# EnvironmentMonitorV6_0.net
KiCad netlist of a schematic drawn in EAGLE
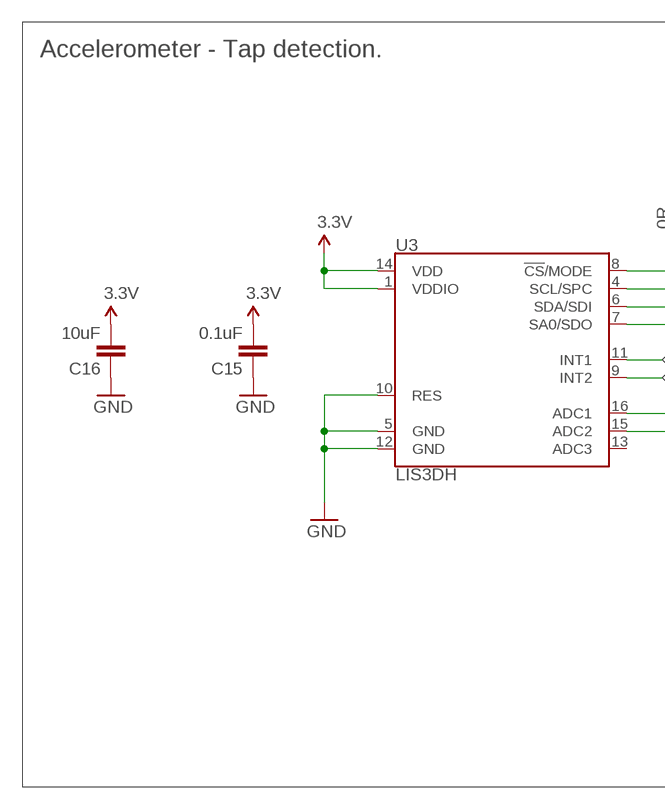
[diagram p0: schematic, sheet 1, part 1 of 2]
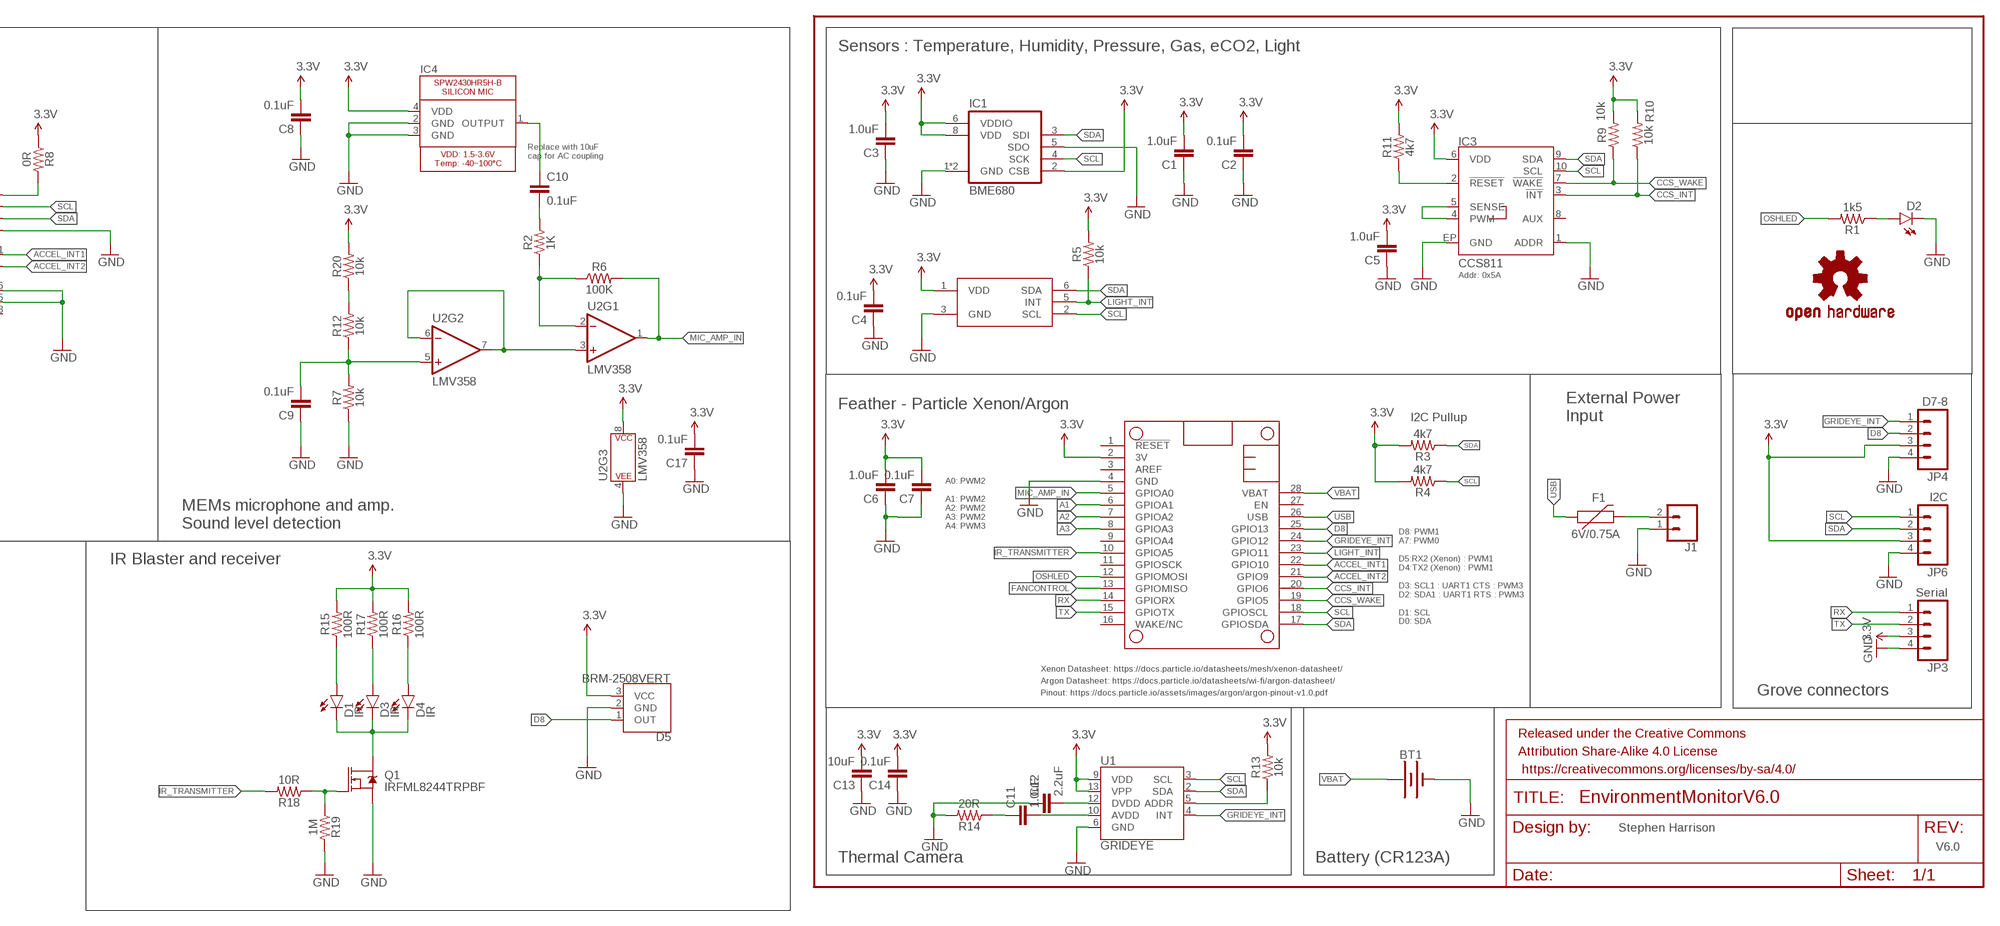
[diagram p1: schematic, sheet 1, part 2 of 2]

(export (version "E")
  (design (tool "Eeschema 10.0.6"))
  (components
    (comp (ref "BT1")
      (value "BATTERY-16340")
      (footprint "eagle-import:BATTERY_16340-HOLDER")
      (libsource (lib "eagle-import") (part "BATTERY-16340"))
    )
    (comp (ref "C1")
      (value "1.0uF")
      (footprint "eagle-import:0805-CAP")
      (libsource (lib "eagle-import") (part "1.0UF-25V-+80/-20(0805){dblquote}"))
    )
    (comp (ref "C2")
      (value "0.1uF")
      (footprint "eagle-import:0805-CAP")
      (libsource (lib "eagle-import") (part "1.0UF-25V-+80/-20(0805){dblquote}"))
    )
    (comp (ref "C3")
      (value "1.0uF")
      (footprint "eagle-import:0805-CAP")
      (libsource (lib "eagle-import") (part "1.0UF-25V-+80/-20(0805){dblquote}"))
    )
    (comp (ref "C4")
      (value "0.1uF")
      (footprint "eagle-import:0805-CAP")
      (libsource (lib "eagle-import") (part "1.0UF-25V-+80/-20(0805){dblquote}"))
    )
    (comp (ref "C5")
      (value "1.0uF")
      (footprint "eagle-import:0805-CAP")
      (libsource (lib "eagle-import") (part "1.0UF-25V-+80/-20(0805){dblquote}"))
    )
    (comp (ref "C6")
      (value "1.0uF")
      (footprint "eagle-import:0805-CAP")
      (libsource (lib "eagle-import") (part "1.0UF-25V-+80/-20(0805){dblquote}"))
    )
    (comp (ref "C7")
      (value "0.1uF")
      (footprint "eagle-import:0805-CAP")
      (libsource (lib "eagle-import") (part "1.0UF-25V-+80/-20(0805){dblquote}"))
    )
    (comp (ref "C8")
      (value "0.1uF")
      (footprint "eagle-import:0805-CAP")
      (libsource (lib "eagle-import") (part "1.0UF-25V-+80/-20(0805){dblquote}"))
    )
    (comp (ref "C9")
      (value "0.1uF")
      (footprint "eagle-import:0805-CAP")
      (libsource (lib "eagle-import") (part "1.0UF-25V-+80/-20(0805){dblquote}"))
    )
    (comp (ref "C10")
      (value "0.1uF")
      (footprint "eagle-import:0805-CAP")
      (libsource (lib "eagle-import") (part "1.0UF-25V-+80/-20(0805){dblquote}"))
    )
    (comp (ref "C11")
      (value "1.0uF")
      (footprint "eagle-import:0805-CAP")
      (libsource (lib "eagle-import") (part "1.0UF-25V-+80/-20(0805){dblquote}"))
    )
    (comp (ref "C12")
      (value "2.2uF")
      (footprint "eagle-import:0805-CAP")
      (libsource (lib "eagle-import") (part "1.0UF-25V-+80/-20(0805){dblquote}"))
    )
    (comp (ref "C13")
      (value "10uF")
      (footprint "eagle-import:0805-CAP")
      (libsource (lib "eagle-import") (part "1.0UF-25V-+80/-20(0805){dblquote}"))
    )
    (comp (ref "C14")
      (value "0.1uF")
      (footprint "eagle-import:0805-CAP")
      (libsource (lib "eagle-import") (part "1.0UF-25V-+80/-20(0805){dblquote}"))
    )
    (comp (ref "C15")
      (value "0.1uF")
      (footprint "eagle-import:0805-CAP")
      (libsource (lib "eagle-import") (part "1.0UF-25V-+80/-20(0805){dblquote}"))
    )
    (comp (ref "C16")
      (value "10uF")
      (footprint "eagle-import:0805-CAP")
      (libsource (lib "eagle-import") (part "1.0UF-25V-+80/-20(0805){dblquote}"))
    )
    (comp (ref "C17")
      (value "0.1uF")
      (footprint "eagle-import:0805-CAP")
      (libsource (lib "eagle-import") (part "1.0UF-25V-+80/-20(0805){dblquote}"))
    )
    (comp (ref "D1")
      (value "IR")
      (footprint "eagle-import:LED-1206")
      (libsource (lib "eagle-import") (part "LED1206"))
    )
    (comp (ref "D2")
      (value "LED1206-BOTTOM")
      (footprint "eagle-import:LED-1206-BOTTOM")
      (libsource (lib "eagle-import") (part "LED1206-BOTTOM"))
    )
    (comp (ref "D3")
      (value "IR")
      (footprint "eagle-import:LED-1206")
      (libsource (lib "eagle-import") (part "LED1206"))
    )
    (comp (ref "D4")
      (value "IR")
      (footprint "eagle-import:LED-1206")
      (libsource (lib "eagle-import") (part "LED1206"))
    )
    (comp (ref "D5")
      (value "BRM-2508VERT")
      (footprint "eagle-import:BRM-2508_VERT")
      (libsource (lib "eagle-import") (part "BRM-2508VERT"))
    )
    (comp (ref "F1")
      (value "6V/0.75A")
      (footprint "eagle-import:1206")
      (libsource (lib "eagle-import") (part "PPTC_THREE-QUARTER-AMP"))
    )
    (comp (ref "FRAME1")
      (value "FRAME-LETTER")
      (footprint "eagle-import:CREATIVE_COMMONS")
      (libsource (lib "eagle-import") (part "FRAME-LETTER"))
    )
    (comp (ref "IC1")
      (value "BME680")
      (footprint "eagle-import:BME680")
      (libsource (lib "eagle-import") (part "BME680"))
    )
    (comp (ref "IC2")
      (value "TCS3472")
      (footprint "eagle-import:FN-6")
      (libsource (lib "eagle-import") (part "TCS3472"))
    )
    (comp (ref "IC3")
      (value "CCS811")
      (footprint "eagle-import:LGA10")
      (libsource (lib "eagle-import") (part "CCS811"))
    )
    (comp (ref "IC4")
      (value "SPW2430HR5H-B")
      (footprint "eagle-import:SPW2430HR5H-B")
      (libsource (lib "eagle-import") (part "SPW2430HR5H-B"))
    )
    (comp (ref "IC5")
      (value "FEATHERWING_NODIM")
      (footprint "eagle-import:FEATHERWING_DIM")
      (libsource (lib "eagle-import") (part "FEATHERWING_NODIM"))
    )
    (comp (ref "J1")
      (value "CONN_02-JST-2MM-SMT")
      (footprint "eagle-import:JST-2-SMD")
      (libsource (lib "eagle-import") (part "CONN_02-JST-2MM-SMT"))
    )
    (comp (ref "JP3")
      (value "Serial")
      (footprint "eagle-import:JST-4-PTH-VERT")
      (libsource (lib "eagle-import") (part "M04JST-PTH-VERT"))
    )
    (comp (ref "JP4")
      (value "D7-8")
      (footprint "eagle-import:JST-4-PTH-VERT")
      (libsource (lib "eagle-import") (part "M04JST-PTH-VERT"))
    )
    (comp (ref "JP6")
      (value "I2C")
      (footprint "eagle-import:JST-4-PTH-VERT")
      (libsource (lib "eagle-import") (part "M04JST-PTH-VERT"))
    )
    (comp (ref "LOGO1")
      (value "OSHW-LOGOM")
      (footprint "eagle-import:OSHW-LOGO-M")
      (libsource (lib "eagle-import") (part "OSHW-LOGOM"))
    )
    (comp (ref "Q1")
      (value "IRFML8244TRPBF")
      (footprint "eagle-import:SOT23-3")
      (libsource (lib "eagle-import") (part "MOSFET-NCH-BSS138"))
    )
    (comp (ref "R1")
      (value "1k5")
      (footprint "eagle-import:0805")
      (libsource (lib "eagle-import") (part "RESISTOR0805"))
    )
    (comp (ref "R2")
      (value "1K")
      (footprint "eagle-import:0805")
      (libsource (lib "eagle-import") (part "RESISTOR0805"))
    )
    (comp (ref "R3")
      (value "4k7")
      (footprint "eagle-import:0805")
      (libsource (lib "eagle-import") (part "RESISTOR0805"))
    )
    (comp (ref "R4")
      (value "4k7")
      (footprint "eagle-import:0805")
      (libsource (lib "eagle-import") (part "RESISTOR0805"))
    )
    (comp (ref "R5")
      (value "10k")
      (footprint "eagle-import:0805")
      (libsource (lib "eagle-import") (part "RESISTOR0805"))
    )
    (comp (ref "R6")
      (value "100K")
      (footprint "eagle-import:0805")
      (libsource (lib "eagle-import") (part "RESISTOR0805"))
    )
    (comp (ref "R7")
      (value "10k")
      (footprint "eagle-import:0805")
      (libsource (lib "eagle-import") (part "RESISTOR0805"))
    )
    (comp (ref "R8")
      (value "0R")
      (footprint "eagle-import:0805")
      (libsource (lib "eagle-import") (part "RESISTOR0805"))
    )
    (comp (ref "R9")
      (value "10k")
      (footprint "eagle-import:0805")
      (libsource (lib "eagle-import") (part "RESISTOR0805"))
    )
    (comp (ref "R10")
      (value "10k")
      (footprint "eagle-import:0805")
      (libsource (lib "eagle-import") (part "RESISTOR0805"))
    )
    (comp (ref "R11")
      (value "4k7")
      (footprint "eagle-import:0805")
      (libsource (lib "eagle-import") (part "RESISTOR0805"))
    )
    (comp (ref "R12")
      (value "10k")
      (footprint "eagle-import:0805")
      (libsource (lib "eagle-import") (part "RESISTOR0805"))
    )
    (comp (ref "R13")
      (value "10k")
      (footprint "eagle-import:0805")
      (libsource (lib "eagle-import") (part "RESISTOR0805"))
    )
    (comp (ref "R14")
      (value "20R")
      (footprint "eagle-import:0805")
      (libsource (lib "eagle-import") (part "RESISTOR0805"))
    )
    (comp (ref "R15")
      (value "100R")
      (footprint "eagle-import:0805")
      (libsource (lib "eagle-import") (part "RESISTOR0805"))
    )
    (comp (ref "R16")
      (value "100R")
      (footprint "eagle-import:0805")
      (libsource (lib "eagle-import") (part "RESISTOR0805"))
    )
    (comp (ref "R17")
      (value "100R")
      (footprint "eagle-import:0805")
      (libsource (lib "eagle-import") (part "RESISTOR0805"))
    )
    (comp (ref "R18")
      (value "10R")
      (footprint "eagle-import:0805")
      (libsource (lib "eagle-import") (part "RESISTOR0805"))
    )
    (comp (ref "R19")
      (value "1M")
      (footprint "eagle-import:0805")
      (libsource (lib "eagle-import") (part "RESISTOR0805"))
    )
    (comp (ref "R20")
      (value "10k")
      (footprint "eagle-import:0805")
      (libsource (lib "eagle-import") (part "RESISTOR0805"))
    )
    (comp (ref "U1")
      (value "GRIDEYE")
      (footprint "eagle-import:GRIDEYE-AMG88")
      (libsource (lib "eagle-import") (part "GRIDEYE"))
    )
    (comp (ref "U2")
      (value "LMV358")
      (footprint "eagle-import:SO08")
      (libsource (lib "eagle-import") (part "LMV358SOIC"))
    )
    (comp (ref "U3")
      (value "LIS3DH")
      (footprint "eagle-import:LGA-16-3X3")
      (libsource (lib "eagle-import") (part "LIS3DH"))
    )
  )
  (nets
    (net (code "1") (name "3.3V") (class "Default")
      (node (ref "C1") (pin "2") (pinfunction "2_2") (pintype "passive"))
      (node (ref "C13") (pin "2") (pinfunction "2_2") (pintype "passive"))
      (node (ref "C14") (pin "2") (pinfunction "2_2") (pintype "passive"))
      (node (ref "C15") (pin "2") (pinfunction "2_2") (pintype "passive"))
      (node (ref "C16") (pin "2") (pinfunction "2_2") (pintype "passive"))
      (node (ref "C17") (pin "2") (pinfunction "2_2") (pintype "passive"))
      (node (ref "C2") (pin "2") (pinfunction "2_2") (pintype "passive"))
      (node (ref "C3") (pin "2") (pinfunction "2_2") (pintype "passive"))
      (node (ref "C4") (pin "2") (pinfunction "2_2") (pintype "passive"))
      (node (ref "C5") (pin "2") (pinfunction "2_2") (pintype "passive"))
      (node (ref "C6") (pin "2") (pinfunction "2_2") (pintype "passive"))
      (node (ref "C7") (pin "2") (pinfunction "2_2") (pintype "passive"))
      (node (ref "C8") (pin "2") (pinfunction "2_2") (pintype "passive"))
      (node (ref "D5") (pin "3") (pinfunction "VCC_3") (pintype "bidirectional"))
      (node (ref "IC1") (pin "2") (pinfunction "CSB_2") (pintype "input"))
      (node (ref "IC1") (pin "6") (pinfunction "VDDIO_6") (pintype "power_in"))
      (node (ref "IC1") (pin "8") (pinfunction "VDD_8") (pintype "power_in"))
      (node (ref "IC2") (pin "1") (pinfunction "VDD_1") (pintype "bidirectional"))
      (node (ref "IC3") (pin "6") (pinfunction "VDD_6") (pintype "bidirectional"))
      (node (ref "IC4") (pin "4") (pinfunction "VDD_4") (pintype "power_in"))
      (node (ref "IC5") (pin "2") (pinfunction "3V_2") (pintype "power_in"))
      (node (ref "JP3") (pin "3") (pinfunction "3_3") (pintype "passive"))
      (node (ref "JP4") (pin "3") (pinfunction "3_3") (pintype "passive"))
      (node (ref "JP6") (pin "3") (pinfunction "3_3") (pintype "passive"))
      (node (ref "R10") (pin "2") (pinfunction "2_2") (pintype "passive"))
      (node (ref "R11") (pin "2") (pinfunction "2_2") (pintype "passive"))
      (node (ref "R13") (pin "2") (pinfunction "2_2") (pintype "passive"))
      (node (ref "R15") (pin "2") (pinfunction "2_2") (pintype "passive"))
      (node (ref "R16") (pin "2") (pinfunction "2_2") (pintype "passive"))
      (node (ref "R17") (pin "2") (pinfunction "2_2") (pintype "passive"))
      (node (ref "R20") (pin "2") (pinfunction "2_2") (pintype "passive"))
      (node (ref "R3") (pin "2") (pinfunction "2_2") (pintype "passive"))
      (node (ref "R4") (pin "2") (pinfunction "2_2") (pintype "passive"))
      (node (ref "R5") (pin "2") (pinfunction "2_2") (pintype "passive"))
      (node (ref "R8") (pin "1") (pinfunction "1_1") (pintype "passive"))
      (node (ref "R9") (pin "2") (pinfunction "2_2") (pintype "passive"))
      (node (ref "U1") (pin "13") (pinfunction "VPP_13") (pintype "bidirectional"))
      (node (ref "U1") (pin "9") (pinfunction "VDD_9") (pintype "bidirectional"))
      (node (ref "U2") (pin "8") (pinfunction "P$V+_8") (pintype "bidirectional"))
      (node (ref "U3") (pin "1") (pinfunction "VDDIO_1") (pintype "bidirectional"))
      (node (ref "U3") (pin "14") (pinfunction "VDD_14") (pintype "bidirectional"))
    )
    (net (code "2") (name "A1") (class "Default")
      (node (ref "IC5") (pin "6") (pinfunction "GPIOA1_6") (pintype "bidirectional"))
    )
    (net (code "3") (name "A2") (class "Default")
      (node (ref "IC5") (pin "7") (pinfunction "GPIOA2_7") (pintype "bidirectional"))
    )
    (net (code "4") (name "A3") (class "Default")
      (node (ref "IC5") (pin "8") (pinfunction "GPIOA3_8") (pintype "bidirectional"))
    )
    (net (code "5") (name "ACCEL_INT1") (class "Default")
      (node (ref "IC5") (pin "22") (pinfunction "GPIO10_22") (pintype "bidirectional"))
      (node (ref "U3") (pin "11") (pinfunction "INT1_11") (pintype "bidirectional"))
    )
    (net (code "6") (name "ACCEL_INT2") (class "Default")
      (node (ref "IC5") (pin "21") (pinfunction "GPIO9_21") (pintype "bidirectional"))
      (node (ref "U3") (pin "9") (pinfunction "INT2_9") (pintype "bidirectional"))
    )
    (net (code "7") (name "CCS_INT") (class "Default")
      (node (ref "IC3") (pin "3") (pinfunction "~{INT}_3") (pintype "bidirectional"))
      (node (ref "IC5") (pin "20") (pinfunction "GPIO6_20") (pintype "bidirectional"))
      (node (ref "R10") (pin "1") (pinfunction "1_1") (pintype "passive"))
    )
    (net (code "8") (name "CCS_WAKE") (class "Default")
      (node (ref "IC3") (pin "7") (pinfunction "~{WAKE}_7") (pintype "bidirectional"))
      (node (ref "IC5") (pin "19") (pinfunction "GPIO5_19") (pintype "bidirectional"))
      (node (ref "R9") (pin "1") (pinfunction "1_1") (pintype "passive"))
    )
    (net (code "9") (name "D8") (class "Default")
      (node (ref "D5") (pin "1") (pinfunction "OUT_1") (pintype "bidirectional"))
      (node (ref "IC5") (pin "25") (pinfunction "GPIO13_25") (pintype "bidirectional"))
      (node (ref "JP4") (pin "2") (pinfunction "2_2") (pintype "passive"))
    )
    (net (code "10") (name "FANCONTROL") (class "Default")
      (node (ref "IC5") (pin "13") (pinfunction "GPIOMISO_13") (pintype "bidirectional"))
    )
    (net (code "11") (name "GND") (class "Default")
      (node (ref "BT1") (pin "P$2") (pinfunction "-_P$2") (pintype "power_in"))
      (node (ref "C1") (pin "1") (pinfunction "1_1") (pintype "passive"))
      (node (ref "C12") (pin "1") (pinfunction "1_1") (pintype "passive"))
      (node (ref "C13") (pin "1") (pinfunction "1_1") (pintype "passive"))
      (node (ref "C14") (pin "1") (pinfunction "1_1") (pintype "passive"))
      (node (ref "C15") (pin "1") (pinfunction "1_1") (pintype "passive"))
      (node (ref "C16") (pin "1") (pinfunction "1_1") (pintype "passive"))
      (node (ref "C17") (pin "1") (pinfunction "1_1") (pintype "passive"))
      (node (ref "C2") (pin "1") (pinfunction "1_1") (pintype "passive"))
      (node (ref "C3") (pin "1") (pinfunction "1_1") (pintype "passive"))
      (node (ref "C4") (pin "1") (pinfunction "1_1") (pintype "passive"))
      (node (ref "C5") (pin "1") (pinfunction "1_1") (pintype "passive"))
      (node (ref "C6") (pin "1") (pinfunction "1_1") (pintype "passive"))
      (node (ref "C7") (pin "1") (pinfunction "1_1") (pintype "passive"))
      (node (ref "C8") (pin "1") (pinfunction "1_1") (pintype "passive"))
      (node (ref "C9") (pin "1") (pinfunction "1_1") (pintype "passive"))
      (node (ref "D2") (pin "C") (pinfunction "C_C") (pintype "passive"))
      (node (ref "D5") (pin "2") (pinfunction "GND_2") (pintype "bidirectional"))
      (node (ref "IC1") (pin "1") (pinfunction "GND_1") (pintype "power_in"))
      (node (ref "IC1") (pin "5") (pinfunction "SDO_5") (pintype "output"))
      (node (ref "IC1") (pin "7") (pinfunction "GND_7") (pintype "power_in"))
      (node (ref "IC2") (pin "3") (pinfunction "GND_3") (pintype "bidirectional"))
      (node (ref "IC3") (pin "1") (pinfunction "ADDR_1") (pintype "bidirectional"))
      (node (ref "IC3") (pin "EP") (pinfunction "GND_EP") (pintype "bidirectional"))
      (node (ref "IC4") (pin "2") (pinfunction "GND_2") (pintype "power_in"))
      (node (ref "IC4") (pin "3") (pinfunction "GND_3") (pintype "power_in"))
      (node (ref "IC5") (pin "4") (pinfunction "GND_4") (pintype "power_in"))
      (node (ref "J1") (pin "1") (pinfunction "2_1") (pintype "passive"))
      (node (ref "JP3") (pin "4") (pinfunction "4_4") (pintype "passive"))
      (node (ref "JP4") (pin "4") (pinfunction "4_4") (pintype "passive"))
      (node (ref "JP6") (pin "4") (pinfunction "4_4") (pintype "passive"))
      (node (ref "Q1") (pin "2") (pinfunction "S_2") (pintype "bidirectional"))
      (node (ref "R14") (pin "2") (pinfunction "2_2") (pintype "passive"))
      (node (ref "R19") (pin "2") (pinfunction "2_2") (pintype "passive"))
      (node (ref "R7") (pin "1") (pinfunction "1_1") (pintype "passive"))
      (node (ref "U1") (pin "6") (pinfunction "GND_6") (pintype "bidirectional"))
      (node (ref "U2") (pin "4") (pinfunction "P$V-_4") (pintype "bidirectional"))
      (node (ref "U3") (pin "10") (pinfunction "RES_10") (pintype "bidirectional"))
      (node (ref "U3") (pin "12") (pinfunction "GND_12") (pintype "bidirectional"))
      (node (ref "U3") (pin "15") (pinfunction "ADC2_15") (pintype "bidirectional"))
      (node (ref "U3") (pin "16") (pinfunction "ADC1_16") (pintype "bidirectional"))
      (node (ref "U3") (pin "5") (pinfunction "GND_5") (pintype "bidirectional"))
      (node (ref "U3") (pin "7") (pinfunction "SA0/SDO_7") (pintype "bidirectional"))
    )
    (net (code "12") (name "GRIDEYE_INT") (class "Default")
      (node (ref "IC5") (pin "24") (pinfunction "GPIO12_24") (pintype "bidirectional"))
      (node (ref "JP4") (pin "1") (pinfunction "1_1") (pintype "passive"))
      (node (ref "U1") (pin "4") (pinfunction "INT_4") (pintype "bidirectional"))
    )
    (net (code "13") (name "IR_TRANSMITTER") (class "Default")
      (node (ref "IC5") (pin "10") (pinfunction "GPIOA5_10") (pintype "bidirectional"))
      (node (ref "R18") (pin "2") (pinfunction "2_2") (pintype "passive"))
    )
    (net (code "14") (name "LIGHT_INT") (class "Default")
      (node (ref "IC2") (pin "5") (pinfunction "INT_5") (pintype "bidirectional"))
      (node (ref "IC5") (pin "23") (pinfunction "GPIO11_23") (pintype "bidirectional"))
      (node (ref "R5") (pin "1") (pinfunction "1_1") (pintype "passive"))
    )
    (net (code "15") (name "MIC_AMP_IN") (class "Default")
      (node (ref "IC5") (pin "5") (pinfunction "GPIOA0_5") (pintype "bidirectional"))
      (node (ref "R6") (pin "2") (pinfunction "2_2") (pintype "passive"))
      (node (ref "U2") (pin "1") (pinfunction "OUT_1") (pintype "output"))
    )
    (net (code "16") (name "Net-(C10-Pad2)") (class "Default")
      (node (ref "C10") (pin "2") (pinfunction "2_2") (pintype "passive"))
      (node (ref "R2") (pin "2") (pinfunction "2_2") (pintype "passive"))
    )
    (net (code "17") (name "Net-(C11-Pad1)") (class "Default")
      (node (ref "C11") (pin "1") (pinfunction "1_1") (pintype "passive"))
      (node (ref "R14") (pin "1") (pinfunction "1_1") (pintype "passive"))
    )
    (net (code "18") (name "Net-(D1-PadA)") (class "Default")
      (node (ref "D1") (pin "A") (pinfunction "A_A") (pintype "passive"))
      (node (ref "R15") (pin "1") (pinfunction "1_1") (pintype "passive"))
    )
    (net (code "19") (name "Net-(D2-PadA)") (class "Default")
      (node (ref "D2") (pin "A") (pinfunction "A_A") (pintype "passive"))
      (node (ref "R1") (pin "1") (pinfunction "1_1") (pintype "passive"))
    )
    (net (code "20") (name "Net-(D3-PadA)") (class "Default")
      (node (ref "D3") (pin "A") (pinfunction "A_A") (pintype "passive"))
      (node (ref "R17") (pin "1") (pinfunction "1_1") (pintype "passive"))
    )
    (net (code "21") (name "Net-(D4-PadA)") (class "Default")
      (node (ref "D4") (pin "A") (pinfunction "A_A") (pintype "passive"))
      (node (ref "R16") (pin "1") (pinfunction "1_1") (pintype "passive"))
    )
    (net (code "22") (name "Net-(IC3-PWM)") (class "Default")
      (node (ref "IC3") (pin "4") (pinfunction "PWM_4") (pintype "bidirectional"))
      (node (ref "IC3") (pin "5") (pinfunction "SENSE_5") (pintype "bidirectional"))
    )
    (net (code "23") (name "Net-(IC3-~{RESET})") (class "Default")
      (node (ref "IC3") (pin "2") (pinfunction "~{RESET}_2") (pintype "bidirectional"))
      (node (ref "R11") (pin "1") (pinfunction "1_1") (pintype "passive"))
    )
    (net (code "24") (name "Net-(IC4-OUTPUT)") (class "Default")
      (node (ref "C10") (pin "1") (pinfunction "1_1") (pintype "passive"))
      (node (ref "IC4") (pin "1") (pinfunction "OUTPUT_1") (pintype "output"))
    )
    (net (code "25") (name "Net-(J1-1)") (class "Default")
      (node (ref "F1") (pin "2") (pinfunction "2_2") (pintype "bidirectional"))
      (node (ref "J1") (pin "2") (pinfunction "1_2") (pintype "passive"))
    )
    (net (code "26") (name "Net-(Q1-D)") (class "Default")
      (node (ref "D1") (pin "C") (pinfunction "C_C") (pintype "passive"))
      (node (ref "D3") (pin "C") (pinfunction "C_C") (pintype "passive"))
      (node (ref "D4") (pin "C") (pinfunction "C_C") (pintype "passive"))
      (node (ref "Q1") (pin "3") (pinfunction "D_3") (pintype "bidirectional"))
    )
    (net (code "27") (name "Net-(Q1-G)") (class "Default")
      (node (ref "Q1") (pin "1") (pinfunction "G_1") (pintype "bidirectional"))
      (node (ref "R18") (pin "1") (pinfunction "1_1") (pintype "passive"))
      (node (ref "R19") (pin "1") (pinfunction "1_1") (pintype "passive"))
    )
    (net (code "28") (name "Net-(R12-Pad2)") (class "Default")
      (node (ref "R12") (pin "2") (pinfunction "2_2") (pintype "passive"))
      (node (ref "R20") (pin "1") (pinfunction "1_1") (pintype "passive"))
    )
    (net (code "29") (name "Net-(U1-ADDR)") (class "Default")
      (node (ref "R13") (pin "1") (pinfunction "1_1") (pintype "passive"))
      (node (ref "U1") (pin "5") (pinfunction "ADDR_5") (pintype "bidirectional"))
    )
    (net (code "30") (name "Net-(U1-AVDD)") (class "Default")
      (node (ref "C11") (pin "2") (pinfunction "2_2") (pintype "passive"))
      (node (ref "U1") (pin "10") (pinfunction "AVDD_10") (pintype "bidirectional"))
    )
    (net (code "31") (name "Net-(U1-DVDD)") (class "Default")
      (node (ref "C12") (pin "2") (pinfunction "2_2") (pintype "passive"))
      (node (ref "U1") (pin "12") (pinfunction "DVDD_12") (pintype "bidirectional"))
    )
    (net (code "32") (name "Net-(U2A-+IN)") (class "Default")
      (node (ref "U2") (pin "3") (pinfunction "+IN_3") (pintype "input"))
      (node (ref "U2") (pin "6") (pinfunction "-IN_6") (pintype "input"))
      (node (ref "U2") (pin "7") (pinfunction "OUT_7") (pintype "output"))
    )
    (net (code "33") (name "Net-(U2A--IN)") (class "Default")
      (node (ref "R2") (pin "1") (pinfunction "1_1") (pintype "passive"))
      (node (ref "R6") (pin "1") (pinfunction "1_1") (pintype "passive"))
      (node (ref "U2") (pin "2") (pinfunction "-IN_2") (pintype "input"))
    )
    (net (code "34") (name "Net-(U2B-+IN)") (class "Default")
      (node (ref "C9") (pin "2") (pinfunction "2_2") (pintype "passive"))
      (node (ref "R12") (pin "1") (pinfunction "1_1") (pintype "passive"))
      (node (ref "R7") (pin "2") (pinfunction "2_2") (pintype "passive"))
      (node (ref "U2") (pin "5") (pinfunction "+IN_5") (pintype "input"))
    )
    (net (code "35") (name "Net-(U3-~{CS}{slash}MODE)") (class "Default")
      (node (ref "R8") (pin "2") (pinfunction "2_2") (pintype "passive"))
      (node (ref "U3") (pin "8") (pinfunction "~{CS}/MODE_8") (pintype "bidirectional"))
    )
    (net (code "36") (name "OSHLED") (class "Default")
      (node (ref "IC5") (pin "12") (pinfunction "GPIOMOSI_12") (pintype "bidirectional"))
      (node (ref "R1") (pin "2") (pinfunction "2_2") (pintype "passive"))
    )
    (net (code "37") (name "RX") (class "Default")
      (node (ref "IC5") (pin "14") (pinfunction "GPIORX_14") (pintype "bidirectional"))
      (node (ref "JP3") (pin "1") (pinfunction "1_1") (pintype "passive"))
    )
    (net (code "38") (name "SCL") (class "Default")
      (node (ref "IC1") (pin "4") (pinfunction "SCK_4") (pintype "input"))
      (node (ref "IC2") (pin "2") (pinfunction "SCL_2") (pintype "bidirectional"))
      (node (ref "IC3") (pin "10") (pinfunction "SCL_10") (pintype "bidirectional"))
      (node (ref "IC5") (pin "18") (pinfunction "GPIOSCL_18") (pintype "bidirectional"))
      (node (ref "JP6") (pin "1") (pinfunction "1_1") (pintype "passive"))
      (node (ref "R4") (pin "1") (pinfunction "1_1") (pintype "passive"))
      (node (ref "U1") (pin "3") (pinfunction "SCL_3") (pintype "bidirectional"))
      (node (ref "U3") (pin "4") (pinfunction "SCL/SPC_4") (pintype "bidirectional"))
    )
    (net (code "39") (name "SDA") (class "Default")
      (node (ref "IC1") (pin "3") (pinfunction "SDI_3") (pintype "input"))
      (node (ref "IC2") (pin "6") (pinfunction "SDA_6") (pintype "bidirectional"))
      (node (ref "IC3") (pin "9") (pinfunction "SDA_9") (pintype "bidirectional"))
      (node (ref "IC5") (pin "17") (pinfunction "GPIOSDA_17") (pintype "bidirectional"))
      (node (ref "JP6") (pin "2") (pinfunction "2_2") (pintype "passive"))
      (node (ref "R3") (pin "1") (pinfunction "1_1") (pintype "passive"))
      (node (ref "U1") (pin "2") (pinfunction "SDA_2") (pintype "bidirectional"))
      (node (ref "U3") (pin "6") (pinfunction "SDA/SDI_6") (pintype "bidirectional"))
    )
    (net (code "40") (name "TX") (class "Default")
      (node (ref "IC5") (pin "15") (pinfunction "GPIOTX_15") (pintype "bidirectional"))
      (node (ref "JP3") (pin "2") (pinfunction "2_2") (pintype "passive"))
    )
    (net (code "41") (name "USB") (class "Default")
      (node (ref "F1") (pin "1") (pinfunction "1_1") (pintype "bidirectional"))
      (node (ref "IC5") (pin "26") (pinfunction "USB_26") (pintype "power_in"))
    )
    (net (code "42") (name "VBAT") (class "Default")
      (node (ref "BT1") (pin "P$1") (pinfunction "+_P$1") (pintype "power_in"))
      (node (ref "IC5") (pin "28") (pinfunction "VBAT_28") (pintype "power_in"))
    )
    (net (code "43") (name "unconnected-(IC3-AUX-Pad8)") (class "Default")
      (node (ref "IC3") (pin "8") (pinfunction "AUX_8") (pintype "bidirectional"))
    )
    (net (code "44") (name "unconnected-(IC5-AREF-Pad3)") (class "Default")
      (node (ref "IC5") (pin "3") (pinfunction "AREF_3") (pintype "passive"))
    )
    (net (code "45") (name "unconnected-(IC5-EN-Pad27)") (class "Default")
      (node (ref "IC5") (pin "27") (pinfunction "EN_27") (pintype "passive"))
    )
    (net (code "46") (name "unconnected-(IC5-GPIOA4-Pad9)") (class "Default")
      (node (ref "IC5") (pin "9") (pinfunction "GPIOA4_9") (pintype "bidirectional"))
    )
    (net (code "47") (name "unconnected-(IC5-GPIOSCK-Pad11)") (class "Default")
      (node (ref "IC5") (pin "11") (pinfunction "GPIOSCK_11") (pintype "bidirectional"))
    )
    (net (code "48") (name "unconnected-(IC5-WAKE{slash}NC-Pad16)") (class "Default")
      (node (ref "IC5") (pin "16") (pinfunction "WAKE/NC_16") (pintype "passive"))
    )
    (net (code "49") (name "unconnected-(IC5-~{RESET}-Pad1)") (class "Default")
      (node (ref "IC5") (pin "1") (pinfunction "~{RESET}_1") (pintype "input"))
    )
    (net (code "50") (name "unconnected-(U3-ADC3-Pad13)") (class "Default")
      (node (ref "U3") (pin "13") (pinfunction "ADC3_13") (pintype "bidirectional"))
    )
  )
)
